# Prototyp_1.net
KiCad netlist of a schematic drawn in EAGLE
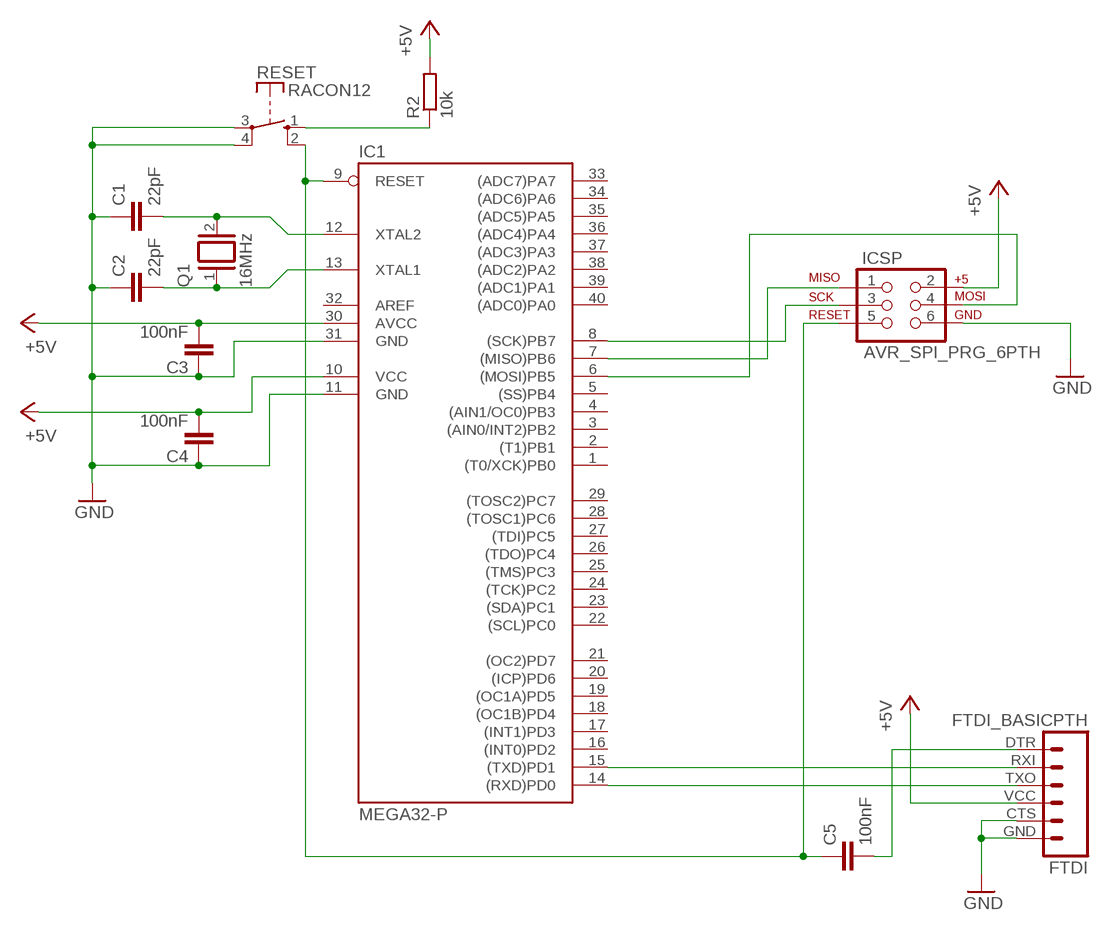
[diagram p0: schematic, sheet 1]

(export (version "E")
  (design (tool "Eeschema 10.0.6"))
  (components
    (comp (ref "C1")
      (value "22pF")
      (footprint "eagle-import:C025-025X050")
      (libsource (lib "eagle-import") (part "resistor_C-EU025-025X050"))
    )
    (comp (ref "C2")
      (value "22pF")
      (footprint "eagle-import:C025-025X050")
      (libsource (lib "eagle-import") (part "resistor_C-EU025-025X050"))
    )
    (comp (ref "C3")
      (value "100nF")
      (footprint "eagle-import:C025-025X050")
      (libsource (lib "eagle-import") (part "C-EU025-025X050"))
    )
    (comp (ref "C4")
      (value "100nF")
      (footprint "eagle-import:C025-025X050")
      (libsource (lib "eagle-import") (part "C-EU025-025X050"))
    )
    (comp (ref "C5")
      (value "100nF")
      (footprint "eagle-import:C025-025X050")
      (libsource (lib "eagle-import") (part "C-EU025-025X050"))
    )
    (comp (ref "FTDI")
      (value "FTDI_BASICPTH")
      (footprint "eagle-import:FTDI_BASIC")
      (libsource (lib "eagle-import") (part "FTDI_BASICPTH"))
    )
    (comp (ref "IC1")
      (value "MEGA32-P")
      (footprint "eagle-import:DIL40")
      (fields (field (name "MPN") "ATMEGA32-16PU"))
      (libsource (lib "eagle-import") (part "MEGA32-P"))
    )
    (comp (ref "ICSP")
      (value "AVR_SPI_PRG_6PTH")
      (footprint "eagle-import:2X3")
      (libsource (lib "eagle-import") (part "AVR_SPI_PRG_6PTH"))
    )
    (comp (ref "Q1")
      (value "16MHz")
      (footprint "eagle-import:Q")
      (libsource (lib "eagle-import") (part "XTAL"))
    )
    (comp (ref "R2")
      (value "10k")
      (footprint "eagle-import:0207_10")
      (libsource (lib "eagle-import") (part "R-EU_0207/10"))
    )
    (comp (ref "RESET")
      (value "RACON12")
      (footprint "eagle-import:RACON12")
      (libsource (lib "eagle-import") (part "RACON12"))
    )
  )
  (nets
    (net (code "1") (name "+5V") (class "Default")
      (node (ref "C3") (pin "2") (pinfunction "2_2") (pintype "passive"))
      (node (ref "C4") (pin "2") (pinfunction "2_2") (pintype "passive"))
      (node (ref "FTDI") (pin "VCC") (pinfunction "4_VCC") (pintype "passive"))
      (node (ref "IC1") (pin "10") (pinfunction "VCC_10") (pintype "power_in"))
      (node (ref "IC1") (pin "30") (pinfunction "AVCC_30") (pintype "power_in"))
      (node (ref "ICSP") (pin "2") (pinfunction "2_2") (pintype "passive"))
      (node (ref "R2") (pin "2") (pinfunction "2_2") (pintype "passive"))
    )
    (net (code "2") (name "GND") (class "Default")
      (node (ref "C1") (pin "1") (pinfunction "1_1") (pintype "passive"))
      (node (ref "C2") (pin "1") (pinfunction "1_1") (pintype "passive"))
      (node (ref "C3") (pin "1") (pinfunction "1_1") (pintype "passive"))
      (node (ref "C4") (pin "1") (pinfunction "1_1") (pintype "passive"))
      (node (ref "FTDI") (pin "CTS") (pinfunction "5_CTS") (pintype "passive"))
      (node (ref "FTDI") (pin "GND") (pinfunction "6_GND") (pintype "passive"))
      (node (ref "IC1") (pin "11") (pinfunction "GND_11") (pintype "power_in"))
      (node (ref "IC1") (pin "31") (pinfunction "GND_31") (pintype "power_in"))
      (node (ref "ICSP") (pin "6") (pinfunction "6_6") (pintype "passive"))
      (node (ref "RESET") (pin "3") (pinfunction "P_3") (pintype "passive"))
      (node (ref "RESET") (pin "4") (pinfunction "P_4") (pintype "passive"))
    )
    (net (code "3") (name "Net-(FTDI-1)") (class "Default")
      (node (ref "C5") (pin "2") (pinfunction "2_2") (pintype "passive"))
      (node (ref "FTDI") (pin "DTR") (pinfunction "1_DTR") (pintype "passive"))
    )
    (net (code "4") (name "Net-(FTDI-2)") (class "Default")
      (node (ref "FTDI") (pin "RXI") (pinfunction "2_RXI") (pintype "passive"))
      (node (ref "IC1") (pin "15") (pinfunction "(TXD)PD1_15") (pintype "bidirectional"))
    )
    (net (code "5") (name "Net-(FTDI-3)") (class "Default")
      (node (ref "FTDI") (pin "TXO") (pinfunction "3_TXO") (pintype "passive"))
      (node (ref "IC1") (pin "14") (pinfunction "(RXD)PD0_14") (pintype "bidirectional"))
    )
    (net (code "6") (name "Net-(IC1-(MISO)PB6)") (class "Default")
      (node (ref "IC1") (pin "7") (pinfunction "(MISO)PB6_7") (pintype "bidirectional"))
      (node (ref "ICSP") (pin "1") (pinfunction "1_1") (pintype "passive"))
    )
    (net (code "7") (name "Net-(IC1-(MOSI)PB5)") (class "Default")
      (node (ref "IC1") (pin "6") (pinfunction "(MOSI)PB5_6") (pintype "bidirectional"))
      (node (ref "ICSP") (pin "4") (pinfunction "4_4") (pintype "passive"))
    )
    (net (code "8") (name "Net-(IC1-(SCK)PB7)") (class "Default")
      (node (ref "IC1") (pin "8") (pinfunction "(SCK)PB7_8") (pintype "bidirectional"))
      (node (ref "ICSP") (pin "3") (pinfunction "3_3") (pintype "passive"))
    )
    (net (code "9") (name "Net-(IC1-RESET)") (class "Default")
      (node (ref "C5") (pin "1") (pinfunction "1_1") (pintype "passive"))
      (node (ref "IC1") (pin "9") (pinfunction "RESET_9") (pintype "input"))
      (node (ref "ICSP") (pin "5") (pinfunction "5_5") (pintype "passive"))
      (node (ref "RESET") (pin "2") (pinfunction "S_2") (pintype "passive"))
    )
    (net (code "10") (name "Net-(IC1-XTAL1)") (class "Default")
      (node (ref "C2") (pin "2") (pinfunction "2_2") (pintype "passive"))
      (node (ref "IC1") (pin "13") (pinfunction "XTAL1_13") (pintype "bidirectional"))
      (node (ref "Q1") (pin "1") (pinfunction "1_1") (pintype "passive"))
    )
    (net (code "11") (name "Net-(IC1-XTAL2)") (class "Default")
      (node (ref "C1") (pin "2") (pinfunction "2_2") (pintype "passive"))
      (node (ref "IC1") (pin "12") (pinfunction "XTAL2_12") (pintype "bidirectional"))
      (node (ref "Q1") (pin "2") (pinfunction "2_2") (pintype "passive"))
    )
    (net (code "12") (name "Net-(R2-Pad1)") (class "Default")
      (node (ref "R2") (pin "1") (pinfunction "1_1") (pintype "passive"))
      (node (ref "RESET") (pin "1") (pinfunction "S_1") (pintype "passive"))
    )
    (net (code "13") (name "unconnected-(IC1-(ADC0)PA0-Pad40)") (class "Default")
      (node (ref "IC1") (pin "40") (pinfunction "(ADC0)PA0_40") (pintype "bidirectional"))
    )
    (net (code "14") (name "unconnected-(IC1-(ADC1)PA1-Pad39)") (class "Default")
      (node (ref "IC1") (pin "39") (pinfunction "(ADC1)PA1_39") (pintype "bidirectional"))
    )
    (net (code "15") (name "unconnected-(IC1-(ADC2)PA2-Pad38)") (class "Default")
      (node (ref "IC1") (pin "38") (pinfunction "(ADC2)PA2_38") (pintype "bidirectional"))
    )
    (net (code "16") (name "unconnected-(IC1-(ADC3)PA3-Pad37)") (class "Default")
      (node (ref "IC1") (pin "37") (pinfunction "(ADC3)PA3_37") (pintype "bidirectional"))
    )
    (net (code "17") (name "unconnected-(IC1-(ADC4)PA4-Pad36)") (class "Default")
      (node (ref "IC1") (pin "36") (pinfunction "(ADC4)PA4_36") (pintype "bidirectional"))
    )
    (net (code "18") (name "unconnected-(IC1-(ADC5)PA5-Pad35)") (class "Default")
      (node (ref "IC1") (pin "35") (pinfunction "(ADC5)PA5_35") (pintype "bidirectional"))
    )
    (net (code "19") (name "unconnected-(IC1-(ADC6)PA6-Pad34)") (class "Default")
      (node (ref "IC1") (pin "34") (pinfunction "(ADC6)PA6_34") (pintype "bidirectional"))
    )
    (net (code "20") (name "unconnected-(IC1-(ADC7)PA7-Pad33)") (class "Default")
      (node (ref "IC1") (pin "33") (pinfunction "(ADC7)PA7_33") (pintype "bidirectional"))
    )
    (net (code "21") (name "unconnected-(IC1-(AIN0{slash}INT2)PB2-Pad3)") (class "Default")
      (node (ref "IC1") (pin "3") (pinfunction "(AIN0/INT2)PB2_3") (pintype "bidirectional"))
    )
    (net (code "22") (name "unconnected-(IC1-(AIN1{slash}OC0)PB3-Pad4)") (class "Default")
      (node (ref "IC1") (pin "4") (pinfunction "(AIN1/OC0)PB3_4") (pintype "bidirectional"))
    )
    (net (code "23") (name "unconnected-(IC1-(ICP)PD6-Pad20)") (class "Default")
      (node (ref "IC1") (pin "20") (pinfunction "(ICP)PD6_20") (pintype "bidirectional"))
    )
    (net (code "24") (name "unconnected-(IC1-(INT0)PD2-Pad16)") (class "Default")
      (node (ref "IC1") (pin "16") (pinfunction "(INT0)PD2_16") (pintype "bidirectional"))
    )
    (net (code "25") (name "unconnected-(IC1-(INT1)PD3-Pad17)") (class "Default")
      (node (ref "IC1") (pin "17") (pinfunction "(INT1)PD3_17") (pintype "bidirectional"))
    )
    (net (code "26") (name "unconnected-(IC1-(OC1A)PD5-Pad19)") (class "Default")
      (node (ref "IC1") (pin "19") (pinfunction "(OC1A)PD5_19") (pintype "bidirectional"))
    )
    (net (code "27") (name "unconnected-(IC1-(OC1B)PD4-Pad18)") (class "Default")
      (node (ref "IC1") (pin "18") (pinfunction "(OC1B)PD4_18") (pintype "bidirectional"))
    )
    (net (code "28") (name "unconnected-(IC1-(OC2)PD7-Pad21)") (class "Default")
      (node (ref "IC1") (pin "21") (pinfunction "(OC2)PD7_21") (pintype "bidirectional"))
    )
    (net (code "29") (name "unconnected-(IC1-(SCL)PC0-Pad22)") (class "Default")
      (node (ref "IC1") (pin "22") (pinfunction "(SCL)PC0_22") (pintype "bidirectional"))
    )
    (net (code "30") (name "unconnected-(IC1-(SDA)PC1-Pad23)") (class "Default")
      (node (ref "IC1") (pin "23") (pinfunction "(SDA)PC1_23") (pintype "bidirectional"))
    )
    (net (code "31") (name "unconnected-(IC1-(SS)PB4-Pad5)") (class "Default")
      (node (ref "IC1") (pin "5") (pinfunction "(SS)PB4_5") (pintype "bidirectional"))
    )
    (net (code "32") (name "unconnected-(IC1-(T0{slash}XCK)PB0-Pad1)") (class "Default")
      (node (ref "IC1") (pin "1") (pinfunction "(T0/XCK)PB0_1") (pintype "bidirectional"))
    )
    (net (code "33") (name "unconnected-(IC1-(T1)PB1-Pad2)") (class "Default")
      (node (ref "IC1") (pin "2") (pinfunction "(T1)PB1_2") (pintype "bidirectional"))
    )
    (net (code "34") (name "unconnected-(IC1-(TCK)PC2-Pad24)") (class "Default")
      (node (ref "IC1") (pin "24") (pinfunction "(TCK)PC2_24") (pintype "bidirectional"))
    )
    (net (code "35") (name "unconnected-(IC1-(TDI)PC5-Pad27)") (class "Default")
      (node (ref "IC1") (pin "27") (pinfunction "(TDI)PC5_27") (pintype "bidirectional"))
    )
    (net (code "36") (name "unconnected-(IC1-(TDO)PC4-Pad26)") (class "Default")
      (node (ref "IC1") (pin "26") (pinfunction "(TDO)PC4_26") (pintype "bidirectional"))
    )
    (net (code "37") (name "unconnected-(IC1-(TMS)PC3-Pad25)") (class "Default")
      (node (ref "IC1") (pin "25") (pinfunction "(TMS)PC3_25") (pintype "bidirectional"))
    )
    (net (code "38") (name "unconnected-(IC1-(TOSC1)PC6-Pad28)") (class "Default")
      (node (ref "IC1") (pin "28") (pinfunction "(TOSC1)PC6_28") (pintype "bidirectional"))
    )
    (net (code "39") (name "unconnected-(IC1-(TOSC2)PC7-Pad29)") (class "Default")
      (node (ref "IC1") (pin "29") (pinfunction "(TOSC2)PC7_29") (pintype "bidirectional"))
    )
    (net (code "40") (name "unconnected-(IC1-AREF-Pad32)") (class "Default")
      (node (ref "IC1") (pin "32") (pinfunction "AREF_32") (pintype "passive"))
    )
  )
)
